# Schematic.net
KiCad netlist of a schematic drawn in EasyEDA
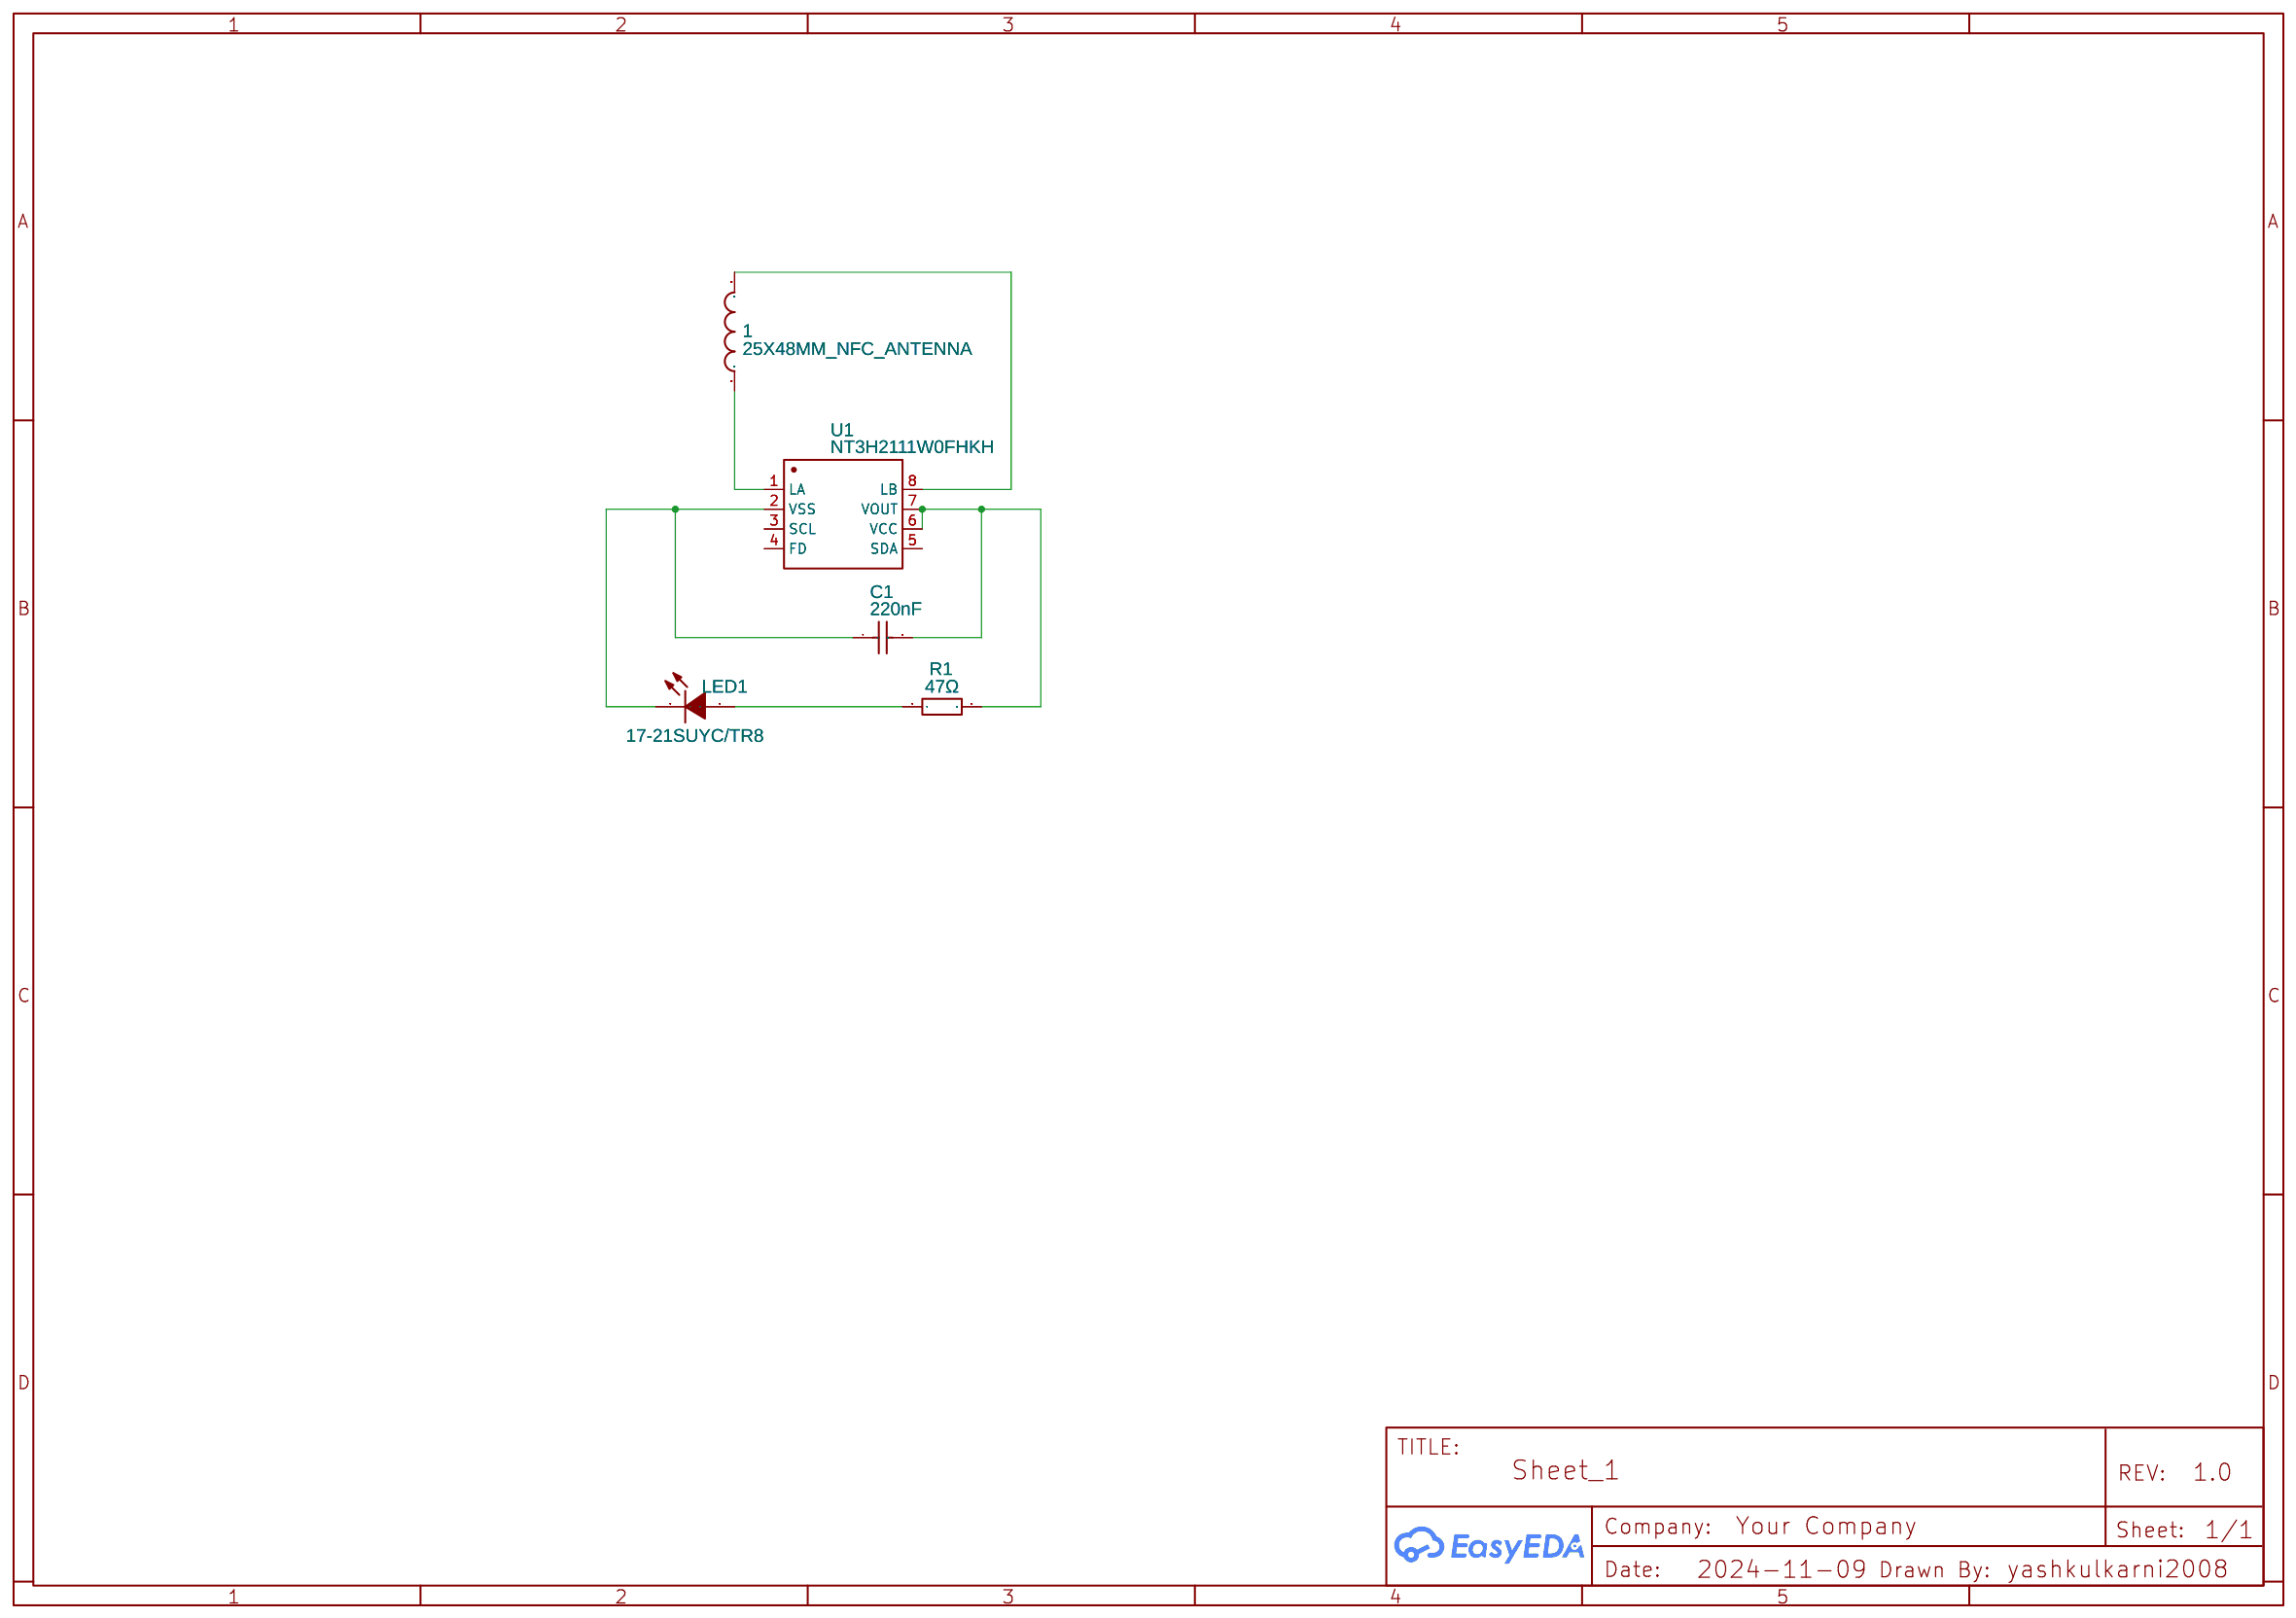
[diagram p0: schematic sheet]

(export (version "E")
  (design (tool "Eeschema 10.0.6"))
  (components
    (comp (ref "1") (value "25X48MM_NFC_ANTENNA") (libsource (lib "") (part "25X48MM_NFC_ANTENNA")))
    (comp (ref "C1")
      (value "220nF")
      (fields
        (field (name "Manufacturer Part") "CL10B224KA8NNNC")
        (field (name "Manufacturer") "SAMSUNG(三星)")
      )
      (libsource (lib "") (part "CL10B224KA8NNNC"))
    )
    (comp (ref "LED1")
      (value "17-21SUYC/TR8")
      (fields (field (name "Manufacturer Part") "KT-0805黄灯") (field (name "Manufacturer") "KENTO"))
      (libsource (lib "") (part "17-21SUYC/TR8"))
    )
    (comp (ref "R1")
      (value "47Ω")
      (fields
        (field (name "Manufacturer Part") "0603WAF470JT5E")
        (field (name "Manufacturer") "UNI-ROYAL(厚声)")
      )
      (libsource (lib "") (part "0603WAF470JT5E"))
    )
    (comp (ref "U1")
      (value "NT3H2111W0FHKH")
      (fields (field (name "Manufacturer") "NXP(恩智浦)"))
      (libsource (lib "") (part "NT3H2111W0FHKH"))
    )
  )
  (nets
    (net (code "1") (name "Net-(LED1-+)") (class "Default")
      (node (ref "LED1") (pin "1") (pinfunction "+_1") (pintype "unspecified"))
      (node (ref "R1") (pin "1") (pinfunction "1_1") (pintype "input"))
    )
    (net (code "2") (name "Net-(LED1--)") (class "Default")
      (node (ref "C1") (pin "1") (pinfunction "1_1") (pintype "input"))
      (node (ref "LED1") (pin "2") (pinfunction "-_2") (pintype "unspecified"))
      (node (ref "U1") (pin "2") (pinfunction "VSS_2") (pintype "unspecified"))
    )
    (net (code "3") (name "Net-(U1-LA)") (class "Default")
      (node (ref "1") (pin "P$1") (pinfunction "P$1_P$1") (pintype "bidirectional"))
      (node (ref "U1") (pin "1") (pinfunction "LA_1") (pintype "unspecified"))
    )
    (net (code "4") (name "Net-(U1-LB)") (class "Default")
      (node (ref "1") (pin "P$2") (pinfunction "P$2_P$2") (pintype "bidirectional"))
      (node (ref "U1") (pin "8") (pinfunction "LB_8") (pintype "unspecified"))
    )
    (net (code "5") (name "Net-(U1-VCC)") (class "Default")
      (node (ref "C1") (pin "2") (pinfunction "2_2") (pintype "input"))
      (node (ref "R1") (pin "2") (pinfunction "2_2") (pintype "input"))
      (node (ref "U1") (pin "6") (pinfunction "VCC_6") (pintype "unspecified"))
      (node (ref "U1") (pin "7") (pinfunction "VOUT_7") (pintype "unspecified"))
    )
    (net (code "6") (name "unconnected-(U1-FD-Pad4)") (class "Default")
      (node (ref "U1") (pin "4") (pinfunction "FD_4") (pintype "unspecified"))
    )
    (net (code "7") (name "unconnected-(U1-SCL-Pad3)") (class "Default")
      (node (ref "U1") (pin "3") (pinfunction "SCL_3") (pintype "unspecified"))
    )
    (net (code "8") (name "unconnected-(U1-SDA-Pad5)") (class "Default")
      (node (ref "U1") (pin "5") (pinfunction "SDA_5") (pintype "unspecified"))
    )
  )
)
